# HM-RC-8_Remote-v03-019.net
KiCad netlist of a schematic drawn in EAGLE
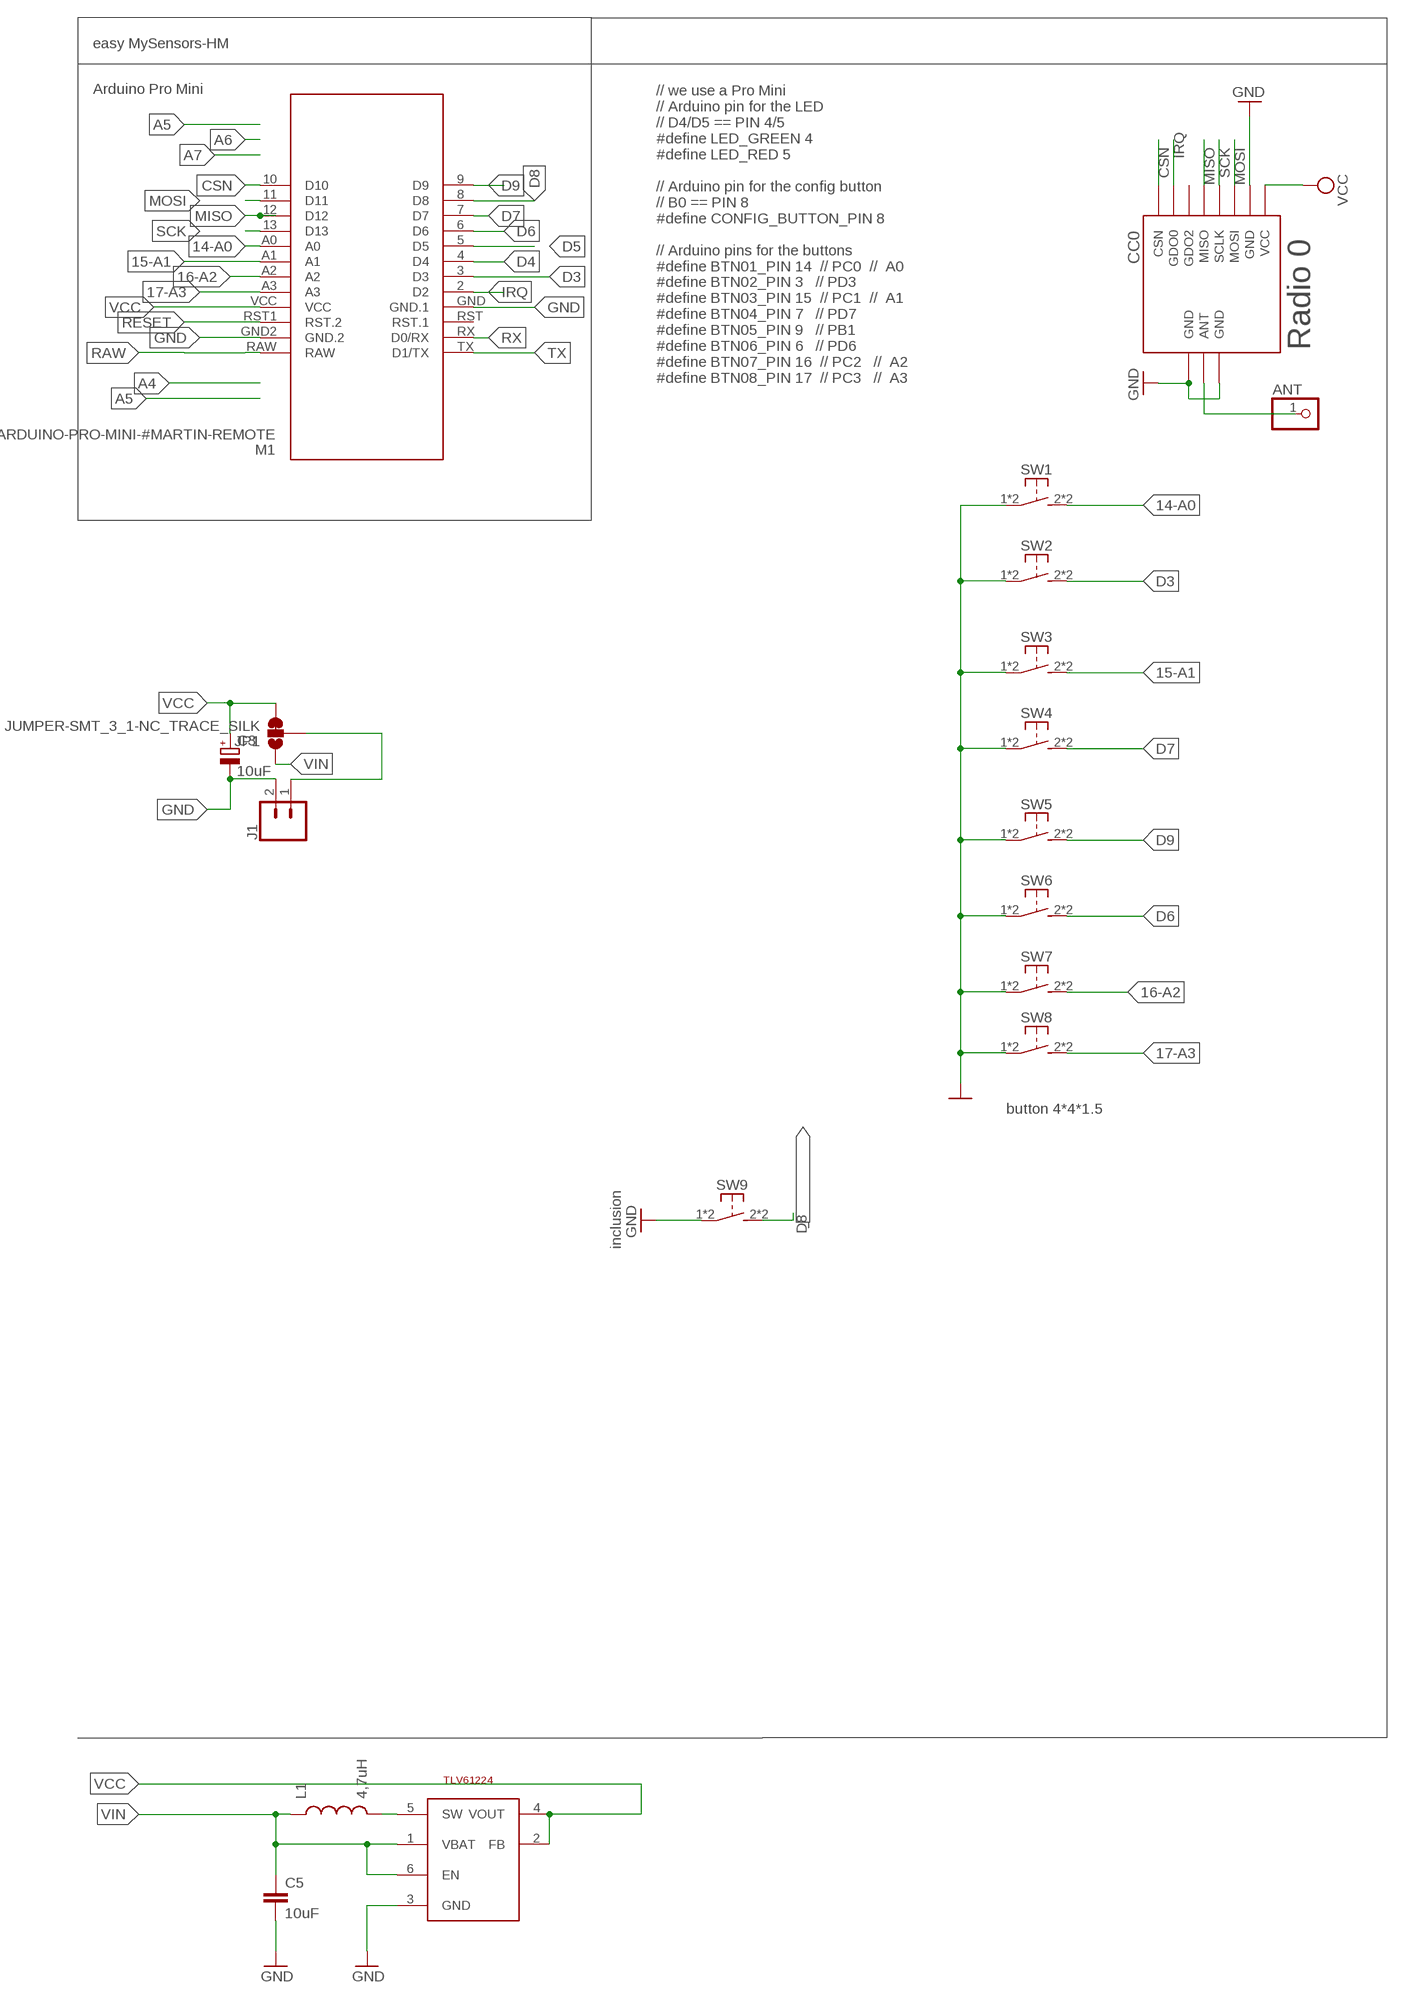
[diagram p0: schematic, sheet 1]

(export (version "E")
  (design (tool "Eeschema 10.0.6"))
  (components
    (comp (ref "ANT")
      (value "PINHD-1X1")
      (footprint "eagle-import:1X01")
      (libsource (lib "eagle-import") (part "PINHD-1X1"))
    )
    (comp (ref "C3")
      (value "10uF")
      (footprint "eagle-import:SMC_C")
      (libsource (lib "eagle-import") (part "CPOL-EUSMCC"))
    )
    (comp (ref "C5")
      (value "10uF")
      (footprint "eagle-import:0805")
      (libsource (lib "eagle-import") (part "CAP0805"))
    )
    (comp (ref "CC0")
      (value "CC1101")
      (footprint "eagle-import:CC1101_MODULE1_SMD")
      (libsource (lib "eagle-import") (part "CC1101_MODULE1SMD"))
    )
    (comp (ref "J1")
      (value "CONN_02PTH3")
      (footprint "eagle-import:1X02_LONGPADS")
      (libsource (lib "eagle-import") (part "CONN_02PTH3"))
    )
    (comp (ref "JP1")
      (value "JUMPER-SMT_3_1-NC_TRACE_SILK")
      (footprint "eagle-import:SMT-JUMPER_3_1-NC_TRACE_SILK")
      (libsource (lib "eagle-import") (part "JUMPER-SMT_3_1-NC_TRACE_SILK"))
    )
    (comp (ref "L1")
      (value "4,7uH")
      (footprint "eagle-import:0805")
      (libsource (lib "eagle-import") (part "INDUCTOR0805"))
    )
    (comp (ref "M1")
      (value "ARDUINO-PRO-MINI-#MARTIN-REMOTE")
      (footprint "eagle-import:ARDUINO-PRO-MINI#NP-MARTIN-REMOTE")
      (libsource (lib "eagle-import") (part "ARDUINO-PRO-MINI-#MARTIN-REMOTE"))
    )
    (comp (ref "STEPUP")
      (value "TLV61224")
      (footprint "eagle-import:SOT23-6L")
      (libsource (lib "eagle-import") (part "TI-TLV61224"))
    )
    (comp (ref "SW1")
      (value "SW-TACTILE-TL3305")
      (footprint "eagle-import:TL3305")
      (libsource (lib "eagle-import") (part "SW-TACTILE-TL3305"))
    )
    (comp (ref "SW2")
      (value "SW-TACTILE-TL3305")
      (footprint "eagle-import:TL3305")
      (libsource (lib "eagle-import") (part "SW-TACTILE-TL3305"))
    )
    (comp (ref "SW3")
      (value "SW-TACTILE-TL3305")
      (footprint "eagle-import:TL3305")
      (libsource (lib "eagle-import") (part "SW-TACTILE-TL3305"))
    )
    (comp (ref "SW4")
      (value "SW-TACTILE-TL3305")
      (footprint "eagle-import:TL3305")
      (libsource (lib "eagle-import") (part "SW-TACTILE-TL3305"))
    )
    (comp (ref "SW5")
      (value "SW-TACTILE-TL3305")
      (footprint "eagle-import:TL3305")
      (libsource (lib "eagle-import") (part "SW-TACTILE-TL3305"))
    )
    (comp (ref "SW6")
      (value "SW-TACTILE-TL3305")
      (footprint "eagle-import:TL3305")
      (libsource (lib "eagle-import") (part "SW-TACTILE-TL3305"))
    )
    (comp (ref "SW7")
      (value "SW-TACTILE-TL3305")
      (footprint "eagle-import:TL3305")
      (libsource (lib "eagle-import") (part "SW-TACTILE-TL3305"))
    )
    (comp (ref "SW8")
      (value "SW-TACTILE-TL3305")
      (footprint "eagle-import:TL3305")
      (libsource (lib "eagle-import") (part "SW-TACTILE-TL3305"))
    )
    (comp (ref "SW9")
      (value "SW-TACTILE-TL3305")
      (footprint "eagle-import:TL3305")
      (libsource (lib "eagle-import") (part "SW-TACTILE-TL3305"))
    )
  )
  (nets
    (net (code "1") (name "14-A0") (class "Default")
      (node (ref "M1") (pin "A0") (pinfunction "A0_A0") (pintype "bidirectional"))
      (node (ref "SW1") (pin "2") (pinfunction "S1_2") (pintype "passive"))
      (node (ref "SW1") (pin "3") (pinfunction "S1_3") (pintype "passive"))
    )
    (net (code "2") (name "15-A1") (class "Default")
      (node (ref "M1") (pin "A1") (pinfunction "A1_A1") (pintype "bidirectional"))
      (node (ref "SW3") (pin "2") (pinfunction "S1_2") (pintype "passive"))
      (node (ref "SW3") (pin "3") (pinfunction "S1_3") (pintype "passive"))
    )
    (net (code "3") (name "16-A2") (class "Default")
      (node (ref "M1") (pin "A2") (pinfunction "A2_A2") (pintype "bidirectional"))
      (node (ref "SW7") (pin "2") (pinfunction "S1_2") (pintype "passive"))
      (node (ref "SW7") (pin "3") (pinfunction "S1_3") (pintype "passive"))
    )
    (net (code "4") (name "17-A3") (class "Default")
      (node (ref "M1") (pin "A3") (pinfunction "A3_A3") (pintype "bidirectional"))
      (node (ref "SW8") (pin "2") (pinfunction "S1_2") (pintype "passive"))
      (node (ref "SW8") (pin "3") (pinfunction "S1_3") (pintype "passive"))
    )
    (net (code "9") (name "CSN") (class "Default")
      (node (ref "CC0") (pin "CSN") (pinfunction "CSN_CSN") (pintype "bidirectional"))
      (node (ref "M1") (pin "10") (pinfunction "D10_10") (pintype "bidirectional"))
    )
    (net (code "10") (name "D3") (class "Default")
      (node (ref "M1") (pin "3") (pinfunction "D3_3") (pintype "bidirectional"))
      (node (ref "SW2") (pin "2") (pinfunction "S1_2") (pintype "passive"))
      (node (ref "SW2") (pin "3") (pinfunction "S1_3") (pintype "passive"))
    )
    (net (code "11") (name "D4") (class "Default")
      (node (ref "M1") (pin "4") (pinfunction "D4_4") (pintype "bidirectional"))
    )
    (net (code "12") (name "D5") (class "Default")
      (node (ref "M1") (pin "5") (pinfunction "D5_5") (pintype "bidirectional"))
    )
    (net (code "13") (name "D6") (class "Default")
      (node (ref "M1") (pin "6") (pinfunction "D6_6") (pintype "bidirectional"))
      (node (ref "SW6") (pin "2") (pinfunction "S1_2") (pintype "passive"))
      (node (ref "SW6") (pin "3") (pinfunction "S1_3") (pintype "passive"))
    )
    (net (code "14") (name "D7") (class "Default")
      (node (ref "M1") (pin "7") (pinfunction "D7_7") (pintype "bidirectional"))
      (node (ref "SW4") (pin "2") (pinfunction "S1_2") (pintype "passive"))
      (node (ref "SW4") (pin "3") (pinfunction "S1_3") (pintype "passive"))
    )
    (net (code "15") (name "D8") (class "Default")
      (node (ref "M1") (pin "8") (pinfunction "D8_8") (pintype "bidirectional"))
      (node (ref "SW9") (pin "2") (pinfunction "S1_2") (pintype "passive"))
      (node (ref "SW9") (pin "3") (pinfunction "S1_3") (pintype "passive"))
    )
    (net (code "16") (name "D9") (class "Default")
      (node (ref "M1") (pin "9") (pinfunction "D9_9") (pintype "bidirectional"))
      (node (ref "SW5") (pin "2") (pinfunction "S1_2") (pintype "passive"))
      (node (ref "SW5") (pin "3") (pinfunction "S1_3") (pintype "passive"))
    )
    (net (code "17") (name "GND") (class "Default")
      (node (ref "C3") (pin "-") (pinfunction "-_-") (pintype "passive"))
      (node (ref "C5") (pin "2") (pinfunction "2_2") (pintype "passive"))
      (node (ref "CC0") (pin "GND@0") (pinfunction "GND_GND@0") (pintype "power_in"))
      (node (ref "CC0") (pin "GND@1") (pinfunction "GND_GND@1") (pintype "power_in"))
      (node (ref "CC0") (pin "GND@2") (pinfunction "GND_GND@2") (pintype "power_in"))
      (node (ref "J1") (pin "2") (pinfunction "2_2") (pintype "passive"))
      (node (ref "M1") (pin "GND") (pinfunction "GND.1_GND") (pintype "power_in"))
      (node (ref "M1") (pin "GND2") (pinfunction "GND.2_GND2") (pintype "power_in"))
      (node (ref "STEPUP") (pin "3") (pinfunction "GND_3") (pintype "power_in"))
      (node (ref "SW1") (pin "1") (pinfunction "P1_1") (pintype "passive"))
      (node (ref "SW1") (pin "4") (pinfunction "P1_4") (pintype "passive"))
      (node (ref "SW2") (pin "1") (pinfunction "P1_1") (pintype "passive"))
      (node (ref "SW2") (pin "4") (pinfunction "P1_4") (pintype "passive"))
      (node (ref "SW3") (pin "1") (pinfunction "P1_1") (pintype "passive"))
      (node (ref "SW3") (pin "4") (pinfunction "P1_4") (pintype "passive"))
      (node (ref "SW4") (pin "1") (pinfunction "P1_1") (pintype "passive"))
      (node (ref "SW4") (pin "4") (pinfunction "P1_4") (pintype "passive"))
      (node (ref "SW5") (pin "1") (pinfunction "P1_1") (pintype "passive"))
      (node (ref "SW5") (pin "4") (pinfunction "P1_4") (pintype "passive"))
      (node (ref "SW6") (pin "1") (pinfunction "P1_1") (pintype "passive"))
      (node (ref "SW6") (pin "4") (pinfunction "P1_4") (pintype "passive"))
      (node (ref "SW7") (pin "1") (pinfunction "P1_1") (pintype "passive"))
      (node (ref "SW7") (pin "4") (pinfunction "P1_4") (pintype "passive"))
      (node (ref "SW8") (pin "1") (pinfunction "P1_1") (pintype "passive"))
      (node (ref "SW8") (pin "4") (pinfunction "P1_4") (pintype "passive"))
      (node (ref "SW9") (pin "1") (pinfunction "P1_1") (pintype "passive"))
      (node (ref "SW9") (pin "4") (pinfunction "P1_4") (pintype "passive"))
    )
    (net (code "18") (name "IRQ") (class "Default")
      (node (ref "CC0") (pin "GDO0") (pinfunction "GDO0_GDO0") (pintype "bidirectional"))
      (node (ref "M1") (pin "2") (pinfunction "D2_2") (pintype "bidirectional"))
    )
    (net (code "19") (name "MISO") (class "Default")
      (node (ref "CC0") (pin "MISO") (pinfunction "MISO_MISO") (pintype "bidirectional"))
      (node (ref "M1") (pin "12") (pinfunction "D12_12") (pintype "bidirectional"))
    )
    (net (code "20") (name "MOSI") (class "Default")
      (node (ref "CC0") (pin "MOSI") (pinfunction "MOSI_MOSI") (pintype "bidirectional"))
      (node (ref "M1") (pin "11") (pinfunction "D11_11") (pintype "bidirectional"))
    )
    (net (code "21") (name "Net-(ANT-Pad1)") (class "Default")
      (node (ref "ANT") (pin "1") (pinfunction "1_1") (pintype "passive"))
      (node (ref "CC0") (pin "ANT") (pinfunction "ANT_ANT") (pintype "output"))
    )
    (net (code "22") (name "Net-(J1-Pad1)") (class "Default")
      (node (ref "J1") (pin "1") (pinfunction "1_1") (pintype "passive"))
      (node (ref "JP1") (pin "2") (pinfunction "2_2") (pintype "passive"))
    )
    (net (code "23") (name "Net-(STEPUP-SW)") (class "Default")
      (node (ref "L1") (pin "2") (pinfunction "2_2") (pintype "passive"))
      (node (ref "STEPUP") (pin "5") (pinfunction "SW_5") (pintype "power_in"))
    )
    (net (code "24") (name "RAW") (class "Default")
      (node (ref "M1") (pin "RAW") (pinfunction "RAW_RAW") (pintype "power_in"))
    )
    (net (code "25") (name "RESET") (class "Default")
      (node (ref "M1") (pin "RST1") (pinfunction "RST.2_RST1") (pintype "bidirectional"))
    )
    (net (code "26") (name "RX") (class "Default")
      (node (ref "M1") (pin "RX") (pinfunction "D0/RX_RX") (pintype "bidirectional"))
    )
    (net (code "27") (name "SCK") (class "Default")
      (node (ref "CC0") (pin "SCLK") (pinfunction "SCLK_SCLK") (pintype "bidirectional"))
      (node (ref "M1") (pin "13") (pinfunction "D13_13") (pintype "bidirectional"))
    )
    (net (code "28") (name "TX") (class "Default")
      (node (ref "M1") (pin "TX") (pinfunction "D1/TX_TX") (pintype "bidirectional"))
    )
    (net (code "29") (name "VCC") (class "Default")
      (node (ref "C3") (pin "+") (pinfunction "+_+") (pintype "passive"))
      (node (ref "CC0") (pin "VCC") (pinfunction "VCC_VCC") (pintype "power_in"))
      (node (ref "JP1") (pin "3") (pinfunction "3_3") (pintype "passive"))
      (node (ref "M1") (pin "VCC") (pinfunction "VCC_VCC") (pintype "power_in"))
      (node (ref "STEPUP") (pin "2") (pinfunction "FB_2") (pintype "input"))
      (node (ref "STEPUP") (pin "4") (pinfunction "VOUT_4") (pintype "power_in"))
    )
    (net (code "30") (name "VIN") (class "Default")
      (node (ref "C5") (pin "1") (pinfunction "1_1") (pintype "passive"))
      (node (ref "JP1") (pin "1") (pinfunction "1_1") (pintype "passive"))
      (node (ref "L1") (pin "1") (pinfunction "1_1") (pintype "passive"))
      (node (ref "STEPUP") (pin "1") (pinfunction "VBAT_1") (pintype "power_in"))
      (node (ref "STEPUP") (pin "6") (pinfunction "EN_6") (pintype "input"))
    )
    (net (code "31") (name "unconnected-(CC0-PadGDO2)") (class "Default")
      (node (ref "CC0") (pin "GDO2") (pinfunction "GDO2_GDO2") (pintype "bidirectional"))
    )
    (net (code "32") (name "unconnected-(M1-RST.1-PadRST)") (class "Default")
      (node (ref "M1") (pin "RST") (pinfunction "RST.1_RST") (pintype "bidirectional"))
    )
  )
)
